# PWM-DCBOOST-NIXIE.net
KiCad netlist of a schematic drawn in Altium Designer
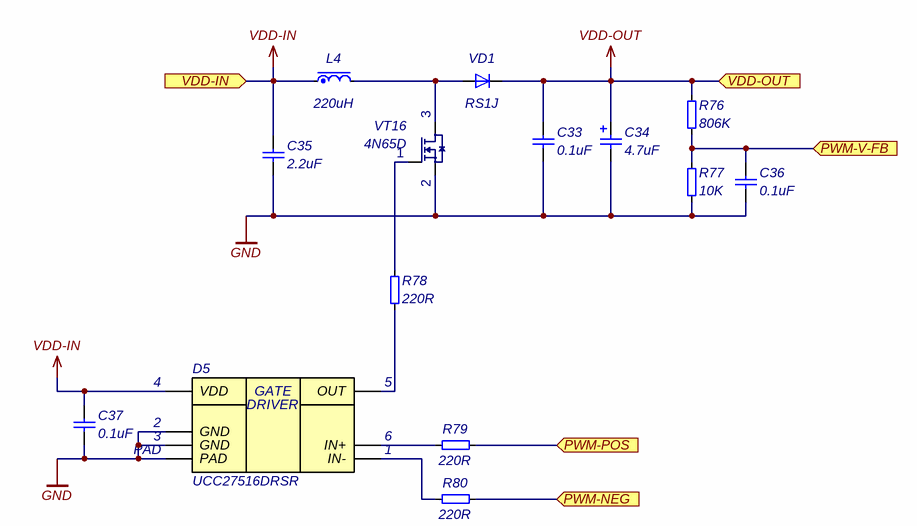
[diagram p0: PWM-DCBOOST-NIXIE.SchDoc]

(export (version "E")
  (design (tool "Eeschema 10.0.6"))
  (components
    (comp (ref "C33")
      (value "0.1uF")
      (footprint "C1210")
      (fields
        (field (name "PART NUMBER") "1210-X7R-250V-0.1uF±10%")
        (field (name "VOLTAGE") "250V")
        (field (name "TOLERANCE") "10%")
      )
      (libsource (lib "ATB") (part "C"))
    )
    (comp (ref "C34")
      (value "4.7uF")
      (footprint "SMD_8X10.5MM")
      (fields
        (field (name "PART NUMBER") "ECAPSMD-4.7UF-400V-20%-10000h")
        (field (name "VOLTAGE") "400V")
        (field (name "TOLERANCE") "20%")
      )
      (libsource (lib "ATB") (part "C_pol"))
    )
    (comp (ref "C35")
      (value "2.2uF")
      (footprint "C1210")
      (fields
        (field (name "PART NUMBER") "1210-X7R-100V-2.2uF±10%")
        (field (name "VOLTAGE") "100V")
        (field (name "TOLERANCE") "10%")
      )
      (libsource (lib "ATB") (part "C"))
    )
    (comp (ref "C36")
      (value "0.1uF")
      (footprint "C0402")
      (fields
        (field (name "PART NUMBER") "0402-X7R-16V-0.1uF±10%")
        (field (name "VOLTAGE") "16V")
        (field (name "TOLERANCE") "10%")
      )
      (libsource (lib "ATB") (part "C"))
    )
    (comp (ref "C37")
      (value "0.1uF")
      (footprint "C0402")
      (fields
        (field (name "PART NUMBER") "0402-X7R-16V-0.1uF±10%")
        (field (name "VOLTAGE") "16V")
        (field (name "TOLERANCE") "10%")
      )
      (libsource (lib "ATB") (part "C"))
    )
    (comp (ref "D5")
      (value "UCC27516DRSR")
      (footprint "S-PWSON-N6")
      (description "Low Side 4.5V~18V 4A SON-6(3x3) Gate Drive")
      (fields (field (name "MANUFACTURER") "Texas Instruments"))
      (libsource (lib "ATB") (part "UCC27516"))
    )
    (comp (ref "L4")
      (value "220uH")
      (footprint "CDRH127")
      (fields
        (field (name "PART NUMBER") "SLH1207S-221k-1.16A")
        (field (name "TOLERANCE") "20%")
        (field (name "MANUFACTURER") "Sunltech Tech")
      )
      (libsource (lib "ATB") (part "L"))
    )
    (comp (ref "R76")
      (value "806K")
      (footprint "R_0805")
      (fields
        (field (name "PART NUMBER") "0805-0.125W-806K-100ppm±1%")
        (field (name "TOLERANCE") "1%")
        (field (name "MANUFACTURER") "Yageo")
      )
      (libsource (lib "ATB") (part "R"))
    )
    (comp (ref "R77")
      (value "10K")
      (footprint "R_0805")
      (fields
        (field (name "PART NUMBER") "0805-0.125W-10K-200ppm±1%")
        (field (name "TOLERANCE") "1%")
        (field (name "MANUFACTURER") "Yageo")
      )
      (libsource (lib "ATB") (part "R"))
    )
    (comp (ref "R78")
      (value "220R")
      (footprint "R_0402")
      (fields
        (field (name "PART NUMBER") "0402-0.0625W-220R-100ppm±1%")
        (field (name "TOLERANCE") "1%")
        (field (name "MANUFACTURER") "Yageo")
      )
      (libsource (lib "ATB") (part "R"))
    )
    (comp (ref "R79")
      (value "220R")
      (footprint "R_0402")
      (fields
        (field (name "PART NUMBER") "0402-0.0625W-220R-100ppm±1%")
        (field (name "TOLERANCE") "1%")
        (field (name "MANUFACTURER") "Yageo")
      )
      (libsource (lib "ATB") (part "R"))
    )
    (comp (ref "R80")
      (value "220R")
      (footprint "R_0402")
      (fields
        (field (name "PART NUMBER") "0402-0.0625W-220R-100ppm±1%")
        (field (name "TOLERANCE") "1%")
        (field (name "MANUFACTURER") "Yageo")
      )
      (libsource (lib "ATB") (part "R"))
    )
    (comp (ref "VD1")
      (value "RS1J")
      (footprint "SMA")
      (description "600V 1.3V@1A 250ns 1A SMA(DO-214AC) Switching Diode")
      (fields (field (name "MANUFACTURER") "WPMtek"))
      (libsource (lib "ATB") (part "Diod"))
    )
    (comp (ref "VT16")
      (value "4N65D")
      (footprint "TO-252-2L")
      (description "650V 4A 2.5Ω TO-252 MOSFET\r\n650V 4A 2.5Ω TO-252 MOSFET")
      (fields (field (name "VOLTAGE") "650V") (field (name "MANUFACTURER") "MDD"))
      (libsource (lib "ATB") (part "MOSFET-N"))
    )
  )
  (nets
    (net (code "1") (name "/PWM-NEG") (class "Default")
      (node (ref "R80") (pin "2") (pinfunction "2_2") (pintype "passive"))
    )
    (net (code "2") (name "/PWM-POS") (class "Default")
      (node (ref "R79") (pin "2") (pinfunction "2_2") (pintype "passive"))
    )
    (net (code "3") (name "/PWM-V-FB") (class "Default")
      (node (ref "C36") (pin "1") (pinfunction "1_1") (pintype "passive"))
      (node (ref "R76") (pin "2") (pinfunction "2_2") (pintype "passive"))
      (node (ref "R77") (pin "1") (pinfunction "1_1") (pintype "passive"))
    )
    (net (code "4") (name "GND") (class "Default")
      (node (ref "C33") (pin "2") (pinfunction "2_2") (pintype "passive"))
      (node (ref "C34") (pin "2") (pinfunction "2_2") (pintype "passive"))
      (node (ref "C35") (pin "2") (pinfunction "2_2") (pintype "passive"))
      (node (ref "C36") (pin "2") (pinfunction "2_2") (pintype "passive"))
      (node (ref "C37") (pin "2") (pinfunction "2_2") (pintype "passive"))
      (node (ref "D5") (pin "2") (pinfunction "GND_2") (pintype "passive"))
      (node (ref "D5") (pin "3") (pinfunction "GND_3") (pintype "passive"))
      (node (ref "D5") (pin "PAD") (pinfunction "PAD_PAD") (pintype "passive"))
      (node (ref "R77") (pin "2") (pinfunction "2_2") (pintype "passive"))
      (node (ref "VT16") (pin "2") (pinfunction "S_2") (pintype "passive"))
    )
    (net (code "5") (name "Net-(D5-IN+)") (class "Default")
      (node (ref "D5") (pin "6") (pinfunction "IN+_6") (pintype "passive"))
      (node (ref "R79") (pin "1") (pinfunction "1_1") (pintype "passive"))
    )
    (net (code "6") (name "Net-(D5-IN-)") (class "Default")
      (node (ref "D5") (pin "1") (pinfunction "IN-_1") (pintype "passive"))
      (node (ref "R80") (pin "1") (pinfunction "1_1") (pintype "passive"))
    )
    (net (code "7") (name "Net-(D5-OUT)") (class "Default")
      (node (ref "D5") (pin "5") (pinfunction "OUT_5") (pintype "passive"))
      (node (ref "R78") (pin "2") (pinfunction "2_2") (pintype "passive"))
    )
    (net (code "8") (name "Net-(VD1-A)") (class "Default")
      (node (ref "L4") (pin "2") (pinfunction "2_2") (pintype "passive"))
      (node (ref "VD1") (pin "2") (pinfunction "A_2") (pintype "passive"))
      (node (ref "VT16") (pin "3") (pinfunction "D_3") (pintype "passive"))
    )
    (net (code "9") (name "Net-(VT16-G)") (class "Default")
      (node (ref "R78") (pin "1") (pinfunction "1_1") (pintype "passive"))
      (node (ref "VT16") (pin "1") (pinfunction "G_1") (pintype "passive"))
    )
    (net (code "10") (name "VDD-IN") (class "Default")
      (node (ref "C35") (pin "1") (pinfunction "1_1") (pintype "passive"))
      (node (ref "C37") (pin "1") (pinfunction "1_1") (pintype "passive"))
      (node (ref "D5") (pin "4") (pinfunction "VDD_4") (pintype "passive"))
      (node (ref "L4") (pin "1") (pinfunction "1_1") (pintype "passive"))
    )
    (net (code "11") (name "VDD-OUT") (class "Default")
      (node (ref "C33") (pin "1") (pinfunction "1_1") (pintype "passive"))
      (node (ref "C34") (pin "1") (pinfunction "1_1") (pintype "passive"))
      (node (ref "R76") (pin "1") (pinfunction "1_1") (pintype "passive"))
      (node (ref "VD1") (pin "1") (pinfunction "K_1") (pintype "passive"))
    )
  )
)
